# CPN_v1.net
KiCad netlist of a schematic drawn in EAGLE
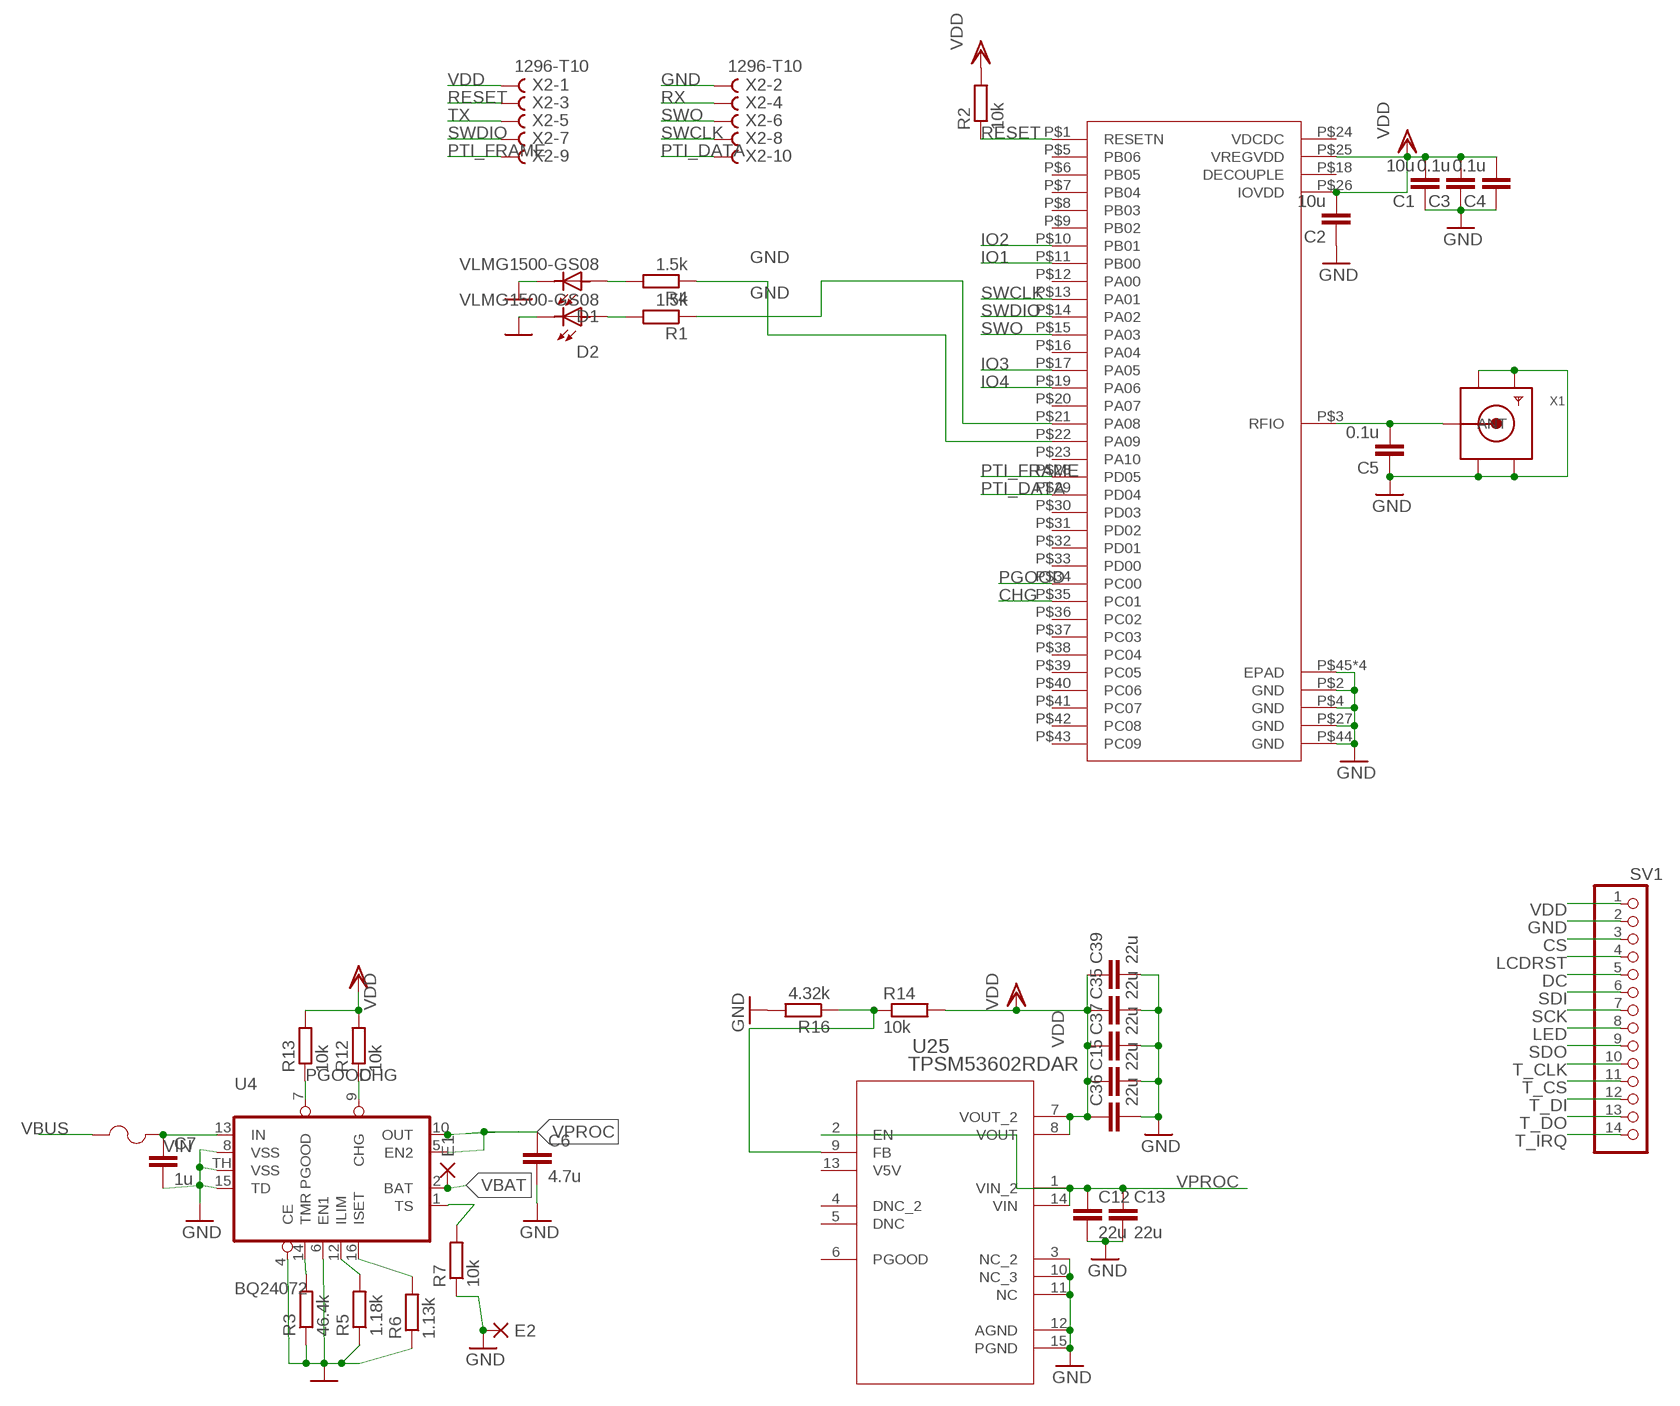
[diagram p0: schematic, sheet 1, part 1 of 2]
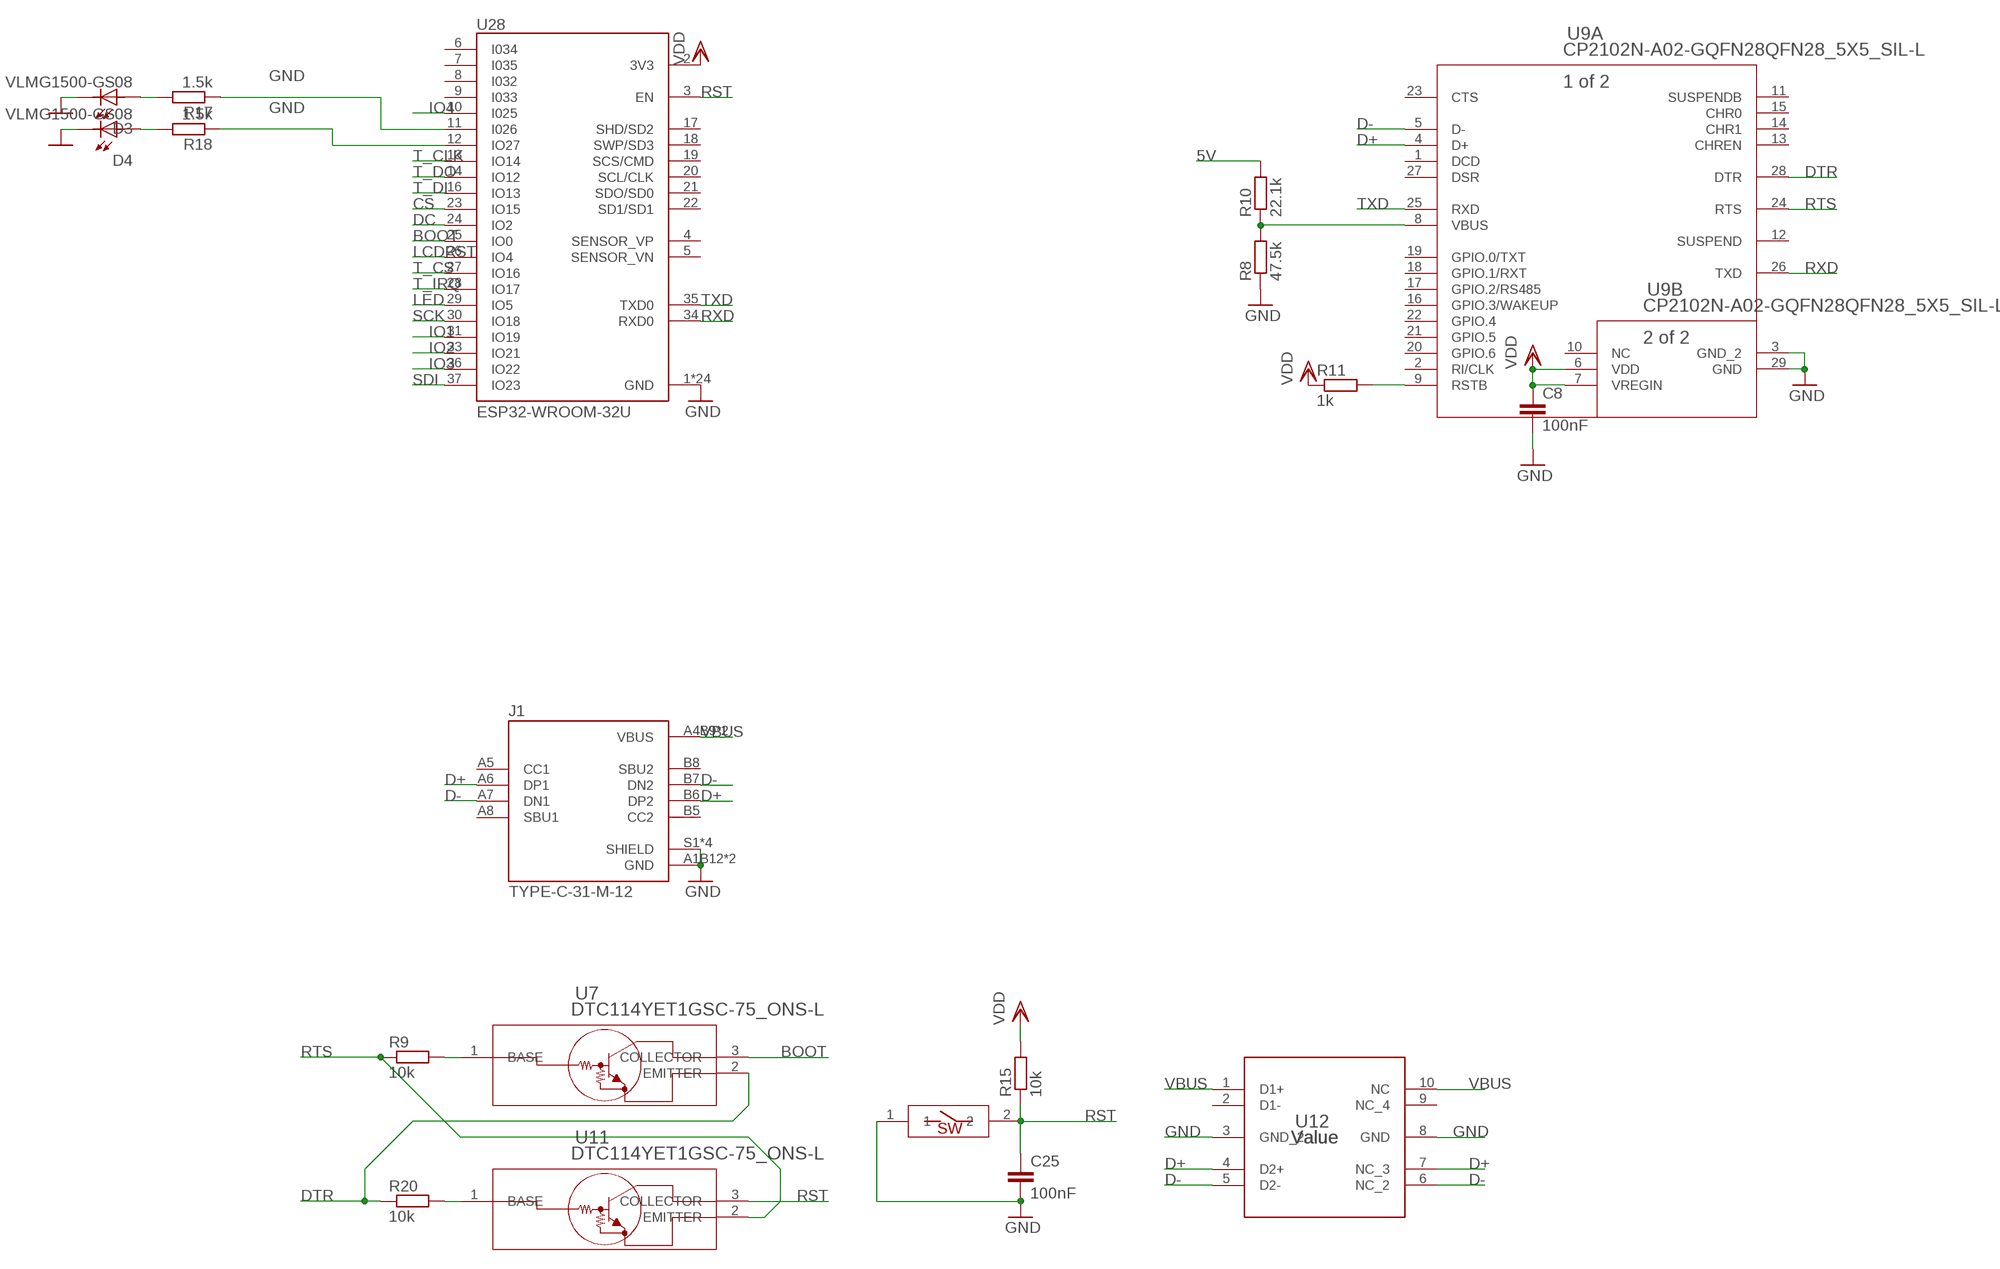
[diagram p1: schematic, sheet 1, part 2 of 2]

(export (version "E")
  (design (tool "Eeschema 10.0.6"))
  (components
    (comp (ref "C1")
      (value "10u")
      (footprint "eagle-import:C0603R")
      (libsource (lib "eagle-import") (part "CC0603R"))
    )
    (comp (ref "C2")
      (value "10u")
      (footprint "eagle-import:C0603R")
      (libsource (lib "eagle-import") (part "CC0603R"))
    )
    (comp (ref "C3")
      (value "0.1u")
      (footprint "eagle-import:C0402")
      (libsource (lib "eagle-import") (part "CC0402"))
    )
    (comp (ref "C4")
      (value "0.1u")
      (footprint "eagle-import:C0402")
      (libsource (lib "eagle-import") (part "CC0402"))
    )
    (comp (ref "C5")
      (value "0.1u")
      (footprint "eagle-import:C0402")
      (libsource (lib "eagle-import") (part "CC0402"))
    )
    (comp (ref "C6")
      (value "4.7u")
      (footprint "eagle-import:C0402")
      (libsource (lib "eagle-import") (part "CC0402"))
    )
    (comp (ref "C7")
      (value "1u")
      (footprint "eagle-import:C0402")
      (libsource (lib "eagle-import") (part "CC0402"))
    )
    (comp (ref "C8")
      (value "100nF")
      (footprint "eagle-import:C0402")
      (libsource (lib "eagle-import") (part "CC0402"))
    )
    (comp (ref "C12")
      (value "22u")
      (footprint "eagle-import:C0603R")
      (libsource (lib "eagle-import") (part "CC0603R"))
    )
    (comp (ref "C13")
      (value "22u")
      (footprint "eagle-import:C0603R")
      (libsource (lib "eagle-import") (part "CC0603R"))
    )
    (comp (ref "C15")
      (value "22u")
      (footprint "eagle-import:C0603R")
      (libsource (lib "eagle-import") (part "CC0603R"))
    )
    (comp (ref "C25")
      (value "100nF")
      (footprint "eagle-import:C0402")
      (libsource (lib "eagle-import") (part "CC0402"))
    )
    (comp (ref "C35")
      (value "22u")
      (footprint "eagle-import:C0603R")
      (libsource (lib "eagle-import") (part "CC0603R"))
    )
    (comp (ref "C36")
      (value "22u")
      (footprint "eagle-import:C0603R")
      (libsource (lib "eagle-import") (part "CC0603R"))
    )
    (comp (ref "C37")
      (value "22u")
      (footprint "eagle-import:C0603R")
      (libsource (lib "eagle-import") (part "CC0603R"))
    )
    (comp (ref "C39")
      (value "22u")
      (footprint "eagle-import:C0603R")
      (libsource (lib "eagle-import") (part "CC0603R"))
    )
    (comp (ref "D1")
      (value "VLMG1500-GS08")
      (footprint "eagle-import:LEDC1005X35N")
      (fields (field (name "MF") "Vishay"))
      (libsource (lib "eagle-import") (part "VLMG1500-GS08"))
    )
    (comp (ref "D2")
      (value "VLMG1500-GS08")
      (footprint "eagle-import:LEDC1005X35N")
      (fields (field (name "MF") "Vishay"))
      (libsource (lib "eagle-import") (part "VLMG1500-GS08"))
    )
    (comp (ref "D3")
      (value "VLMG1500-GS08")
      (footprint "eagle-import:LEDC1005X35N")
      (fields (field (name "MF") "Vishay"))
      (libsource (lib "eagle-import") (part "VLMG1500-GS08"))
    )
    (comp (ref "D4")
      (value "VLMG1500-GS08")
      (footprint "eagle-import:LEDC1005X35N")
      (fields (field (name "MF") "Vishay"))
      (libsource (lib "eagle-import") (part "VLMG1500-GS08"))
    )
    (comp (ref "E1")
      (value "DPADS_PAD-0400-S")
      (footprint "eagle-import:DPADS_0400-S")
      (libsource (lib "eagle-import") (part "DPADS_PAD-0400-S"))
    )
    (comp (ref "E2")
      (value "DPADS_PAD-0400-S")
      (footprint "eagle-import:DPADS_0400-S")
      (libsource (lib "eagle-import") (part "DPADS_PAD-0400-S"))
    )
    (comp (ref "F2")
      (value "1210L050YR1210LSERIES_LTF-L")
      (footprint "eagle-import:1210LSERIES_LTF-L")
      (fields (field (name "MANUFACTURER_PART_NUMBER") "1210L050YR"))
      (libsource (lib "eagle-import") (part "1210L050YR1210LSERIES_LTF-L"))
    )
    (comp (ref "J1")
      (value "TYPE-C-31-M-12")
      (footprint "eagle-import:HRO_TYPE-C-31-M-12")
      (fields (field (name "MF") "HRO Electronics Co., Ltd."))
      (libsource (lib "eagle-import") (part "TYPE-C-31-M-12"))
    )
    (comp (ref "R1")
      (value "1.5k")
      (footprint "eagle-import:R0402")
      (libsource (lib "eagle-import") (part "RR0402"))
    )
    (comp (ref "R2")
      (value "10k")
      (footprint "eagle-import:R0402")
      (libsource (lib "eagle-import") (part "RR0402"))
    )
    (comp (ref "R3")
      (value "46.4k")
      (footprint "eagle-import:R0402")
      (libsource (lib "eagle-import") (part "RR0402"))
    )
    (comp (ref "R4")
      (value "1.5k")
      (footprint "eagle-import:R0402")
      (libsource (lib "eagle-import") (part "RR0402"))
    )
    (comp (ref "R5")
      (value "1.18k")
      (footprint "eagle-import:R0402")
      (libsource (lib "eagle-import") (part "RR0402"))
    )
    (comp (ref "R6")
      (value "1.13k")
      (footprint "eagle-import:R0402")
      (libsource (lib "eagle-import") (part "RR0402"))
    )
    (comp (ref "R7")
      (value "10k")
      (footprint "eagle-import:R0402")
      (libsource (lib "eagle-import") (part "RR0402"))
    )
    (comp (ref "R8")
      (value "47.5k")
      (footprint "eagle-import:R0402")
      (libsource (lib "eagle-import") (part "RR0402"))
    )
    (comp (ref "R9")
      (value "10k")
      (footprint "eagle-import:R0402")
      (libsource (lib "eagle-import") (part "RR0402"))
    )
    (comp (ref "R10")
      (value "22.1k")
      (footprint "eagle-import:R0402")
      (libsource (lib "eagle-import") (part "RR0402"))
    )
    (comp (ref "R11")
      (value "1k")
      (footprint "eagle-import:R0402")
      (libsource (lib "eagle-import") (part "RR0402"))
    )
    (comp (ref "R12")
      (value "10k")
      (footprint "eagle-import:R0402")
      (libsource (lib "eagle-import") (part "RR0402"))
    )
    (comp (ref "R13")
      (value "10k")
      (footprint "eagle-import:R0402")
      (libsource (lib "eagle-import") (part "RR0402"))
    )
    (comp (ref "R14")
      (value "10k")
      (footprint "eagle-import:R0402")
      (libsource (lib "eagle-import") (part "RR0402"))
    )
    (comp (ref "R15")
      (value "10k")
      (footprint "eagle-import:R0402")
      (libsource (lib "eagle-import") (part "RR0402"))
    )
    (comp (ref "R16")
      (value "4.32k")
      (footprint "eagle-import:R0402")
      (libsource (lib "eagle-import") (part "RR0402"))
    )
    (comp (ref "R17")
      (value "1.5k")
      (footprint "eagle-import:R0402")
      (libsource (lib "eagle-import") (part "RR0402"))
    )
    (comp (ref "R18")
      (value "1.5k")
      (footprint "eagle-import:R0402")
      (libsource (lib "eagle-import") (part "RR0402"))
    )
    (comp (ref "R20")
      (value "10k")
      (footprint "eagle-import:R0402")
      (libsource (lib "eagle-import") (part "RR0402"))
    )
    (comp (ref "RESET")
      (value "SMDSWITCH")
      (footprint "eagle-import:RESC4217X170")
      (libsource (lib "eagle-import") (part "SMDSWITCH"))
    )
    (comp (ref "SV1")
      (value "PINHD-1X14")
      (footprint "eagle-import:1X14")
      (libsource (lib "eagle-import") (part "PINHD-1X14"))
    )
    (comp (ref "U$1")
      (value "ZGM230S")
      (footprint "eagle-import:ZGM230S")
      (libsource (lib "eagle-import") (part "ZGM230S"))
    )
    (comp (ref "U4")
      (value "BQ24072")
      (footprint "eagle-import:S-PVQFN-N16")
      (libsource (lib "eagle-import") (part "BQ24072"))
    )
    (comp (ref "U7")
      (value "DTC114YET1GSC-75_ONS-L")
      (footprint "eagle-import:SC-75_ONS-L")
      (fields
        (field (name "MANUFACTURER_PART_NUMBER") "DTC114YET1G")
        (field (name "COPYRIGHT") "Copyright (C) 2018 Accelerated Designs. All rights reserved")
      )
      (libsource (lib "eagle-import") (part "DTC114YET1GSC-75_ONS-L"))
    )
    (comp (ref "U9")
      (value "CP2102N-A02-GQFN28QFN28_5X5_SIL-L")
      (footprint "eagle-import:QFN28_5X5_SIL-L")
      (fields
        (field (name "MANUFACTURER_PART_NUMBER") "CP2102N-A02-GQFN28")
        (field (name "COPYRIGHT") "Copyright (C) 2018 Accelerated Designs. All rights reserved")
      )
      (libsource (lib "eagle-import") (part "CP2102N-A02-GQFN28QFN28_5X5_SIL-L"))
    )
    (comp (ref "U11")
      (value "DTC114YET1GSC-75_ONS-L")
      (footprint "eagle-import:SC-75_ONS-L")
      (fields
        (field (name "MANUFACTURER_PART_NUMBER") "DTC114YET1G")
        (field (name "COPYRIGHT") "Copyright (C) 2018 Accelerated Designs. All rights reserved")
      )
      (libsource (lib "eagle-import") (part "DTC114YET1GSC-75_ONS-L"))
    )
    (comp (ref "U12")
      (value "Value")
      (footprint "eagle-import:DQA0010A")
      (fields (field (name "MANUFACTURER") "Texas Instruments") (field (name "PARTNUMBER") "ESD204DQAR"))
      (libsource (lib "eagle-import") (part "ESD204DQAR"))
    )
    (comp (ref "U25")
      (value "TPSM53602RDAR")
      (footprint "eagle-import:B3QFN15_RDA_TEX")
      (fields (field (name "COPYRIGHT") "Copyright (C) 2018 Accelerated Designs. All rights reserved"))
      (libsource (lib "eagle-import") (part "TPSM53602RDAR"))
    )
    (comp (ref "U28")
      (value "ESP32-WROOM-32U")
      (footprint "eagle-import:XCVR_ESP32-WROOM-32U")
      (fields (field (name "MF") "Espressif Systems"))
      (libsource (lib "eagle-import") (part "ESP32-WROOM-32U"))
    )
    (comp (ref "X1")
      (value "SMACONNECTOR")
      (footprint "eagle-import:SMA90_DIP")
      (libsource (lib "eagle-import") (part "SMACONNECTOR"))
    )
    (comp (ref "X2")
      (value "1296-T10")
      (footprint "eagle-import:1296-10")
      (libsource (lib "eagle-import") (part "1296-T10"))
    )
  )
  (nets
    (net (code "1") (name "/5V") (class "Default")
      (node (ref "R10") (pin "2") (pinfunction "2_2") (pintype "passive"))
    )
    (net (code "2") (name "/BOOT") (class "Default")
      (node (ref "U28") (pin "25") (pinfunction "IO0_25") (pintype "bidirectional"))
      (node (ref "U7") (pin "3") (pinfunction "COLLECTOR_3") (pintype "output"))
    )
    (net (code "3") (name "/CHG") (class "Default")
      (node (ref "R12") (pin "1") (pinfunction "1_1") (pintype "passive"))
      (node (ref "U$1") (pin "P$35") (pinfunction "PC01_P$35") (pintype "bidirectional"))
      (node (ref "U4") (pin "9") (pinfunction "CHG_9") (pintype "bidirectional"))
    )
    (net (code "4") (name "/CS") (class "Default")
      (node (ref "SV1") (pin "3") (pinfunction "3_3") (pintype "passive"))
      (node (ref "U28") (pin "23") (pinfunction "IO15_23") (pintype "bidirectional"))
    )
    (net (code "5") (name "/D+") (class "Default")
      (node (ref "J1") (pin "A6") (pinfunction "DP1_A6") (pintype "bidirectional"))
      (node (ref "J1") (pin "B6") (pinfunction "DP2_B6") (pintype "bidirectional"))
      (node (ref "U12") (pin "4") (pinfunction "D2+_4") (pintype "bidirectional"))
      (node (ref "U12") (pin "7") (pinfunction "NC_3_7") (pintype "passive"))
      (node (ref "U9") (pin "4") (pinfunction "D+_4") (pintype "input"))
    )
    (net (code "6") (name "/D-") (class "Default")
      (node (ref "J1") (pin "A7") (pinfunction "DN1_A7") (pintype "bidirectional"))
      (node (ref "J1") (pin "B7") (pinfunction "DN2_B7") (pintype "bidirectional"))
      (node (ref "U12") (pin "5") (pinfunction "D2-_5") (pintype "bidirectional"))
      (node (ref "U12") (pin "6") (pinfunction "NC_2_6") (pintype "passive"))
      (node (ref "U9") (pin "5") (pinfunction "D-_5") (pintype "input"))
    )
    (net (code "7") (name "/DC") (class "Default")
      (node (ref "SV1") (pin "5") (pinfunction "5_5") (pintype "passive"))
      (node (ref "U28") (pin "24") (pinfunction "IO2_24") (pintype "bidirectional"))
    )
    (net (code "8") (name "/DTR") (class "Default")
      (node (ref "R20") (pin "1") (pinfunction "1_1") (pintype "passive"))
      (node (ref "U7") (pin "2") (pinfunction "EMITTER_2") (pintype "passive"))
      (node (ref "U9") (pin "28") (pinfunction "DTR_28") (pintype "output"))
    )
    (net (code "9") (name "/IO1") (class "Default")
      (node (ref "U$1") (pin "P$11") (pinfunction "PB00_P$11") (pintype "bidirectional"))
      (node (ref "U28") (pin "31") (pinfunction "IO19_31") (pintype "bidirectional"))
    )
    (net (code "10") (name "/IO2") (class "Default")
      (node (ref "U$1") (pin "P$10") (pinfunction "PB01_P$10") (pintype "bidirectional"))
      (node (ref "U28") (pin "33") (pinfunction "IO21_33") (pintype "bidirectional"))
    )
    (net (code "11") (name "/IO3") (class "Default")
      (node (ref "U$1") (pin "P$17") (pinfunction "PA05_P$17") (pintype "bidirectional"))
      (node (ref "U28") (pin "36") (pinfunction "IO22_36") (pintype "bidirectional"))
    )
    (net (code "12") (name "/IO4") (class "Default")
      (node (ref "U$1") (pin "P$19") (pinfunction "PA06_P$19") (pintype "bidirectional"))
      (node (ref "U28") (pin "10") (pinfunction "I025_10") (pintype "bidirectional"))
    )
    (net (code "13") (name "/LCDRST") (class "Default")
      (node (ref "SV1") (pin "4") (pinfunction "4_4") (pintype "passive"))
      (node (ref "U28") (pin "26") (pinfunction "IO4_26") (pintype "bidirectional"))
    )
    (net (code "14") (name "/LED") (class "Default")
      (node (ref "SV1") (pin "8") (pinfunction "8_8") (pintype "passive"))
      (node (ref "U28") (pin "29") (pinfunction "IO5_29") (pintype "bidirectional"))
    )
    (net (code "15") (name "/PGOOD") (class "Default")
      (node (ref "R13") (pin "1") (pinfunction "1_1") (pintype "passive"))
      (node (ref "U$1") (pin "P$34") (pinfunction "PC00_P$34") (pintype "bidirectional"))
      (node (ref "U4") (pin "7") (pinfunction "PGOOD_7") (pintype "bidirectional"))
    )
    (net (code "16") (name "/PTI_DATA") (class "Default")
      (node (ref "U$1") (pin "P$29") (pinfunction "PD04_P$29") (pintype "bidirectional"))
      (node (ref "X2") (pin "10") (pinfunction "B_10") (pintype "passive"))
    )
    (net (code "17") (name "/PTI_FRAME") (class "Default")
      (node (ref "U$1") (pin "P$28") (pinfunction "PD05_P$28") (pintype "bidirectional"))
      (node (ref "X2") (pin "9") (pinfunction "B_9") (pintype "passive"))
    )
    (net (code "18") (name "/RESET") (class "Default")
      (node (ref "R2") (pin "1") (pinfunction "1_1") (pintype "passive"))
      (node (ref "U$1") (pin "P$1") (pinfunction "RESETN_P$1") (pintype "bidirectional"))
      (node (ref "X2") (pin "3") (pinfunction "B_3") (pintype "passive"))
    )
    (net (code "19") (name "/RST") (class "Default")
      (node (ref "C25") (pin "1") (pinfunction "1_1") (pintype "passive"))
      (node (ref "R15") (pin "1") (pinfunction "1_1") (pintype "passive"))
      (node (ref "RESET") (pin "2") (pinfunction "2_2") (pintype "bidirectional"))
      (node (ref "U11") (pin "3") (pinfunction "COLLECTOR_3") (pintype "output"))
      (node (ref "U28") (pin "3") (pinfunction "EN_3") (pintype "input"))
    )
    (net (code "20") (name "/RTS") (class "Default")
      (node (ref "R9") (pin "1") (pinfunction "1_1") (pintype "passive"))
      (node (ref "U11") (pin "2") (pinfunction "EMITTER_2") (pintype "passive"))
      (node (ref "U9") (pin "24") (pinfunction "RTS_24") (pintype "output"))
    )
    (net (code "21") (name "/RX") (class "Default")
      (node (ref "X2") (pin "4") (pinfunction "B_4") (pintype "passive"))
    )
    (net (code "22") (name "/RXD") (class "Default")
      (node (ref "U28") (pin "34") (pinfunction "RXD0_34") (pintype "bidirectional"))
      (node (ref "U9") (pin "26") (pinfunction "TXD_26") (pintype "output"))
    )
    (net (code "23") (name "/SCK") (class "Default")
      (node (ref "SV1") (pin "7") (pinfunction "7_7") (pintype "passive"))
      (node (ref "U28") (pin "30") (pinfunction "IO18_30") (pintype "bidirectional"))
    )
    (net (code "24") (name "/SDI") (class "Default")
      (node (ref "SV1") (pin "6") (pinfunction "6_6") (pintype "passive"))
      (node (ref "U28") (pin "37") (pinfunction "IO23_37") (pintype "bidirectional"))
    )
    (net (code "25") (name "/SDO") (class "Default")
      (node (ref "SV1") (pin "9") (pinfunction "9_9") (pintype "passive"))
    )
    (net (code "26") (name "/SWCLK") (class "Default")
      (node (ref "U$1") (pin "P$13") (pinfunction "PA01_P$13") (pintype "bidirectional"))
      (node (ref "X2") (pin "8") (pinfunction "B_8") (pintype "passive"))
    )
    (net (code "27") (name "/SWDIO") (class "Default")
      (node (ref "U$1") (pin "P$14") (pinfunction "PA02_P$14") (pintype "bidirectional"))
      (node (ref "X2") (pin "7") (pinfunction "B_7") (pintype "passive"))
    )
    (net (code "28") (name "/SWO") (class "Default")
      (node (ref "U$1") (pin "P$15") (pinfunction "PA03_P$15") (pintype "bidirectional"))
      (node (ref "X2") (pin "6") (pinfunction "B_6") (pintype "passive"))
    )
    (net (code "29") (name "/TX") (class "Default")
      (node (ref "X2") (pin "5") (pinfunction "B_5") (pintype "passive"))
    )
    (net (code "30") (name "/TXD") (class "Default")
      (node (ref "U28") (pin "35") (pinfunction "TXD0_35") (pintype "bidirectional"))
      (node (ref "U9") (pin "25") (pinfunction "RXD_25") (pintype "input"))
    )
    (net (code "31") (name "/T_CLK") (class "Default")
      (node (ref "SV1") (pin "10") (pinfunction "10_10") (pintype "passive"))
      (node (ref "U28") (pin "13") (pinfunction "IO14_13") (pintype "bidirectional"))
    )
    (net (code "32") (name "/T_CS") (class "Default")
      (node (ref "SV1") (pin "11") (pinfunction "11_11") (pintype "passive"))
      (node (ref "U28") (pin "27") (pinfunction "IO16_27") (pintype "bidirectional"))
    )
    (net (code "33") (name "/T_DI") (class "Default")
      (node (ref "SV1") (pin "12") (pinfunction "12_12") (pintype "passive"))
      (node (ref "U28") (pin "16") (pinfunction "IO13_16") (pintype "bidirectional"))
    )
    (net (code "34") (name "/T_DO") (class "Default")
      (node (ref "SV1") (pin "13") (pinfunction "13_13") (pintype "passive"))
      (node (ref "U28") (pin "14") (pinfunction "IO12_14") (pintype "bidirectional"))
    )
    (net (code "35") (name "/T_IRQ") (class "Default")
      (node (ref "SV1") (pin "14") (pinfunction "14_14") (pintype "passive"))
      (node (ref "U28") (pin "28") (pinfunction "IO17_28") (pintype "bidirectional"))
    )
    (net (code "36") (name "/VBUS") (class "Default")
      (node (ref "F2") (pin "1") (pinfunction "1_1") (pintype "passive"))
      (node (ref "J1") (pin "A4B9") (pinfunction "VBUS_A4B9") (pintype "power_in"))
      (node (ref "J1") (pin "B4A9") (pinfunction "VBUS_B4A9") (pintype "power_in"))
      (node (ref "U12") (pin "1") (pinfunction "D1+_1") (pintype "bidirectional"))
      (node (ref "U12") (pin "10") (pinfunction "NC_10") (pintype "passive"))
    )
    (net (code "37") (name "/VIN") (class "Default")
      (node (ref "C7") (pin "1") (pinfunction "1_1") (pintype "passive"))
      (node (ref "F2") (pin "2") (pinfunction "2_2") (pintype "passive"))
      (node (ref "U4") (pin "13") (pinfunction "IN_13") (pintype "input"))
    )
    (net (code "38") (name "GND") (class "Default")
      (node (ref "C1") (pin "1") (pinfunction "1_1") (pintype "passive"))
      (node (ref "C12") (pin "2") (pinfunction "2_2") (pintype "passive"))
      (node (ref "C13") (pin "2") (pinfunction "2_2") (pintype "passive"))
      (node (ref "C15") (pin "2") (pinfunction "2_2") (pintype "passive"))
      (node (ref "C2") (pin "1") (pinfunction "1_1") (pintype "passive"))
      (node (ref "C25") (pin "2") (pinfunction "2_2") (pintype "passive"))
      (node (ref "C3") (pin "1") (pinfunction "1_1") (pintype "passive"))
      (node (ref "C35") (pin "2") (pinfunction "2_2") (pintype "passive"))
      (node (ref "C36") (pin "2") (pinfunction "2_2") (pintype "passive"))
      (node (ref "C37") (pin "2") (pinfunction "2_2") (pintype "passive"))
      (node (ref "C39") (pin "2") (pinfunction "2_2") (pintype "passive"))
      (node (ref "C4") (pin "1") (pinfunction "1_1") (pintype "passive"))
      (node (ref "C5") (pin "1") (pinfunction "1_1") (pintype "passive"))
      (node (ref "C6") (pin "2") (pinfunction "2_2") (pintype "passive"))
      (node (ref "C7") (pin "2") (pinfunction "2_2") (pintype "passive"))
      (node (ref "C8") (pin "2") (pinfunction "2_2") (pintype "passive"))
      (node (ref "D1") (pin "2") (pinfunction "2_2") (pintype "passive"))
      (node (ref "D2") (pin "2") (pinfunction "2_2") (pintype "passive"))
      (node (ref "D3") (pin "2") (pinfunction "2_2") (pintype "passive"))
      (node (ref "D4") (pin "2") (pinfunction "2_2") (pintype "passive"))
      (node (ref "E2") (pin "PAD") (pinfunction "P_PAD") (pintype "passive"))
      (node (ref "J1") (pin "A1B12") (pinfunction "GND_A1B12") (pintype "power_in"))
      (node (ref "J1") (pin "B1A12") (pinfunction "GND_B1A12") (pintype "power_in"))
      (node (ref "J1") (pin "S1") (pinfunction "SHIELD_S1") (pintype "passive"))
      (node (ref "J1") (pin "S2") (pinfunction "SHIELD_S2") (pintype "passive"))
      (node (ref "J1") (pin "S3") (pinfunction "SHIELD_S3") (pintype "passive"))
      (node (ref "J1") (pin "S4") (pinfunction "SHIELD_S4") (pintype "passive"))
      (node (ref "R16") (pin "2") (pinfunction "2_2") (pintype "passive"))
      (node (ref "R3") (pin "1") (pinfunction "1_1") (pintype "passive"))
      (node (ref "R5") (pin "1") (pinfunction "1_1") (pintype "passive"))
      (node (ref "R6") (pin "1") (pinfunction "1_1") (pintype "passive"))
      (node (ref "R7") (pin "1") (pinfunction "1_1") (pintype "passive"))
      (node (ref "R8") (pin "1") (pinfunction "1_1") (pintype "passive"))
      (node (ref "RESET") (pin "1") (pinfunction "1_1") (pintype "bidirectional"))
      (node (ref "SV1") (pin "2") (pinfunction "2_2") (pintype "passive"))
      (node (ref "U$1") (pin "P$2") (pinfunction "GND_P$2") (pintype "bidirectional"))
      (node (ref "U$1") (pin "P$27") (pinfunction "GND_P$27") (pintype "bidirectional"))
      (node (ref "U$1") (pin "P$4") (pinfunction "GND_P$4") (pintype "bidirectional"))
      (node (ref "U$1") (pin "P$44") (pinfunction "GND_P$44") (pintype "bidirectional"))
      (node (ref "U$1") (pin "P$45") (pinfunction "EPAD_P$45") (pintype "bidirectional"))
      (node (ref "U$1") (pin "P$46") (pinfunction "EPAD_P$46") (pintype "bidirectional"))
      (node (ref "U$1") (pin "P$47") (pinfunction "EPAD_P$47") (pintype "bidirectional"))
      (node (ref "U$1") (pin "P$48") (pinfunction "EPAD_P$48") (pintype "bidirectional"))
      (node (ref "U12") (pin "3") (pinfunction "GND_2_3") (pintype "power_in"))
      (node (ref "U12") (pin "8") (pinfunction "GND_8") (pintype "power_in"))
      (node (ref "U25") (pin "10") (pinfunction "NC_3_10") (pintype "passive"))
      (node (ref "U25") (pin "11") (pinfunction "NC_11") (pintype "passive"))
      (node (ref "U25") (pin "12") (pinfunction "AGND_12") (pintype "passive"))
      (node (ref "U25") (pin "15") (pinfunction "PGND_15") (pintype "passive"))
      (node (ref "U25") (pin "3") (pinfunction "NC_2_3") (pintype "passive"))
      (node (ref "U28") (pin "1") (pinfunction "GND_1") (pintype "power_in"))
      (node (ref "U28") (pin "15") (pinfunction "GND_15") (pintype "power_in"))
      (node (ref "U28") (pin "38") (pinfunction "GND_38") (pintype "power_in"))
      (node (ref "U28") (pin "G.1") (pinfunction "GND_G.1") (pintype "power_in"))
      (node (ref "U28") (pin "G.10") (pinfunction "GND_G.10") (pintype "power_in"))
      (node (ref "U28") (pin "G.11") (pinfunction "GND_G.11") (pintype "power_in"))
      (node (ref "U28") (pin "G.12") (pinfunction "GND_G.12") (pintype "power_in"))
      (node (ref "U28") (pin "G.13") (pinfunction "GND_G.13") (pintype "power_in"))
      (node (ref "U28") (pin "G.14") (pinfunction "GND_G.14") (pintype "power_in"))
      (node (ref "U28") (pin "G.15") (pinfunction "GND_G.15") (pintype "power_in"))
      (node (ref "U28") (pin "G.16") (pinfunction "GND_G.16") (pintype "power_in"))
      (node (ref "U28") (pin "G.17") (pinfunction "GND_G.17") (pintype "power_in"))
      (node (ref "U28") (pin "G.18") (pinfunction "GND_G.18") (pintype "power_in"))
      (node (ref "U28") (pin "G.19") (pinfunction "GND_G.19") (pintype "power_in"))
      (node (ref "U28") (pin "G.2") (pinfunction "GND_G.2") (pintype "power_in"))
      (node (ref "U28") (pin "G.20") (pinfunction "GND_G.20") (pintype "power_in"))
      (node (ref "U28") (pin "G.21") (pinfunction "GND_G.21") (pintype "power_in"))
      (node (ref "U28") (pin "G.22") (pinfunction "GND_G.22") (pintype "power_in"))
      (node (ref "U28") (pin "G.4") (pinfunction "GND_G.4") (pintype "power_in"))
      (node (ref "U28") (pin "G.5") (pinfunction "GND_G.5") (pintype "power_in"))
      (node (ref "U28") (pin "G.6") (pinfunction "GND_G.6") (pintype "power_in"))
      (node (ref "U28") (pin "G.7") (pinfunction "GND_G.7") (pintype "power_in"))
      (node (ref "U28") (pin "G.8") (pinfunction "GND_G.8") (pintype "power_in"))
      (node (ref "U28") (pin "G.9") (pinfunction "GND_G.9") (pintype "power_in"))
      (node (ref "U4") (pin "15") (pinfunction "TD_15") (pintype "bidirectional"))
      (node (ref "U4") (pin "4") (pinfunction "CE_4") (pintype "bidirectional"))
      (node (ref "U4") (pin "6") (pinfunction "EN1_6") (pintype "bidirectional"))
      (node (ref "U4") (pin "8") (pinfunction "VSS_8") (pintype "power_in"))
      (node (ref "U4") (pin "TH") (pinfunction "VSS_TH") (pintype "power_in"))
      (node (ref "U9") (pin "29") (pinfunction "GND_29") (pintype "passive"))
      (node (ref "U9") (pin "3") (pinfunction "GND_2_3") (pintype "passive"))
      (node (ref "X1") (pin "GND1") (pinfunction "GND1_GND1") (pintype "power_in"))
      (node (ref "X1") (pin "GND2") (pinfunction "GND2_GND2") (pintype "power_in"))
      (node (ref "X1") (pin "GND3") (pinfunction "GND3_GND3") (pintype "power_in"))
      (node (ref "X1") (pin "GND4") (pinfunction "GND4_GND4") (pintype "power_in"))
      (node (ref "X2") (pin "2") (pinfunction "B_2") (pintype "passive"))
    )
    (net (code "39") (name "Net-(D1-Pad1)") (class "Default")
      (node (ref "D1") (pin "1") (pinfunction "1_1") (pintype "passive"))
      (node (ref "R4") (pin "2") (pinfunction "2_2") (pintype "passive"))
    )
    (net (code "40") (name "Net-(D2-Pad1)") (class "Default")
      (node (ref "D2") (pin "1") (pinfunction "1_1") (pintype "passive"))
      (node (ref "R1") (pin "2") (pinfunction "2_2") (pintype "passive"))
    )
    (net (code "41") (name "Net-(D3-Pad1)") (class "Default")
      (node (ref "D3") (pin "1") (pinfunction "1_1") (pintype "passive"))
      (node (ref "R17") (pin "2") (pinfunction "2_2") (pintype "passive"))
    )
    (net (code "42") (name "Net-(D4-Pad1)") (class "Default")
      (node (ref "D4") (pin "1") (pinfunction "1_1") (pintype "passive"))
      (node (ref "R18") (pin "2") (pinfunction "2_2") (pintype "passive"))
    )
    (net (code "43") (name "Net-(U$1-PA08)") (class "Default")
      (node (ref "R1") (pin "1") (pinfunction "1_1") (pintype "passive"))
      (node (ref "U$1") (pin "P$21") (pinfunction "PA08_P$21") (pintype "bidirectional"))
    )
    (net (code "44") (name "Net-(U$1-PA09)") (class "Default")
      (node (ref "R4") (pin "1") (pinfunction "1_1") (pintype "passive"))
      (node (ref "U$1") (pin "P$22") (pinfunction "PA09_P$22") (pintype "bidirectional"))
    )
    (net (code "45") (name "Net-(U$1-RFIO)") (class "Default")
      (node (ref "C5") (pin "2") (pinfunction "2_2") (pintype "passive"))
      (node (ref "U$1") (pin "P$3") (pinfunction "RFIO_P$3") (pintype "bidirectional"))
      (node (ref "X1") (pin "ANTENNA") (pinfunction "ANT_ANTENNA") (pintype "bidirectional"))
    )
    (net (code "46") (name "Net-(U4-ILIM)") (class "Default")
      (node (ref "R5") (pin "2") (pinfunction "2_2") (pintype "passive"))
      (node (ref "U4") (pin "12") (pinfunction "ILIM_12") (pintype "bidirectional"))
    )
    (net (code "47") (name "Net-(U4-ISET)") (class "Default")
      (node (ref "R6") (pin "2") (pinfunction "2_2") (pintype "passive"))
      (node (ref "U4") (pin "16") (pinfunction "ISET_16") (pintype "input"))
    )
    (net (code "48") (name "Net-(U4-TMR)") (class "Default")
      (node (ref "R3") (pin "2") (pinfunction "2_2") (pintype "passive"))
      (node (ref "U4") (pin "14") (pinfunction "TMR_14") (pintype "bidirectional"))
    )
    (net (code "49") (name "Net-(U4-TS)") (class "Default")
      (node (ref "R7") (pin "2") (pinfunction "2_2") (pintype "passive"))
      (node (ref "U4") (pin "1") (pinfunction "TS_1") (pintype "input"))
    )
    (net (code "50") (name "Net-(U7-BASE)") (class "Default")
      (node (ref "R9") (pin "2") (pinfunction "2_2") (pintype "passive"))
      (node (ref "U7") (pin "1") (pinfunction "BASE_1") (pintype "input"))
    )
    (net (code "51") (name "Net-(U9A-RSTB)") (class "Default")
      (node (ref "R11") (pin "2") (pinfunction "2_2") (pintype "passive"))
      (node (ref "U9") (pin "9") (pinfunction "RSTB_9") (pintype "passive"))
    )
    (net (code "52") (name "Net-(U9A-VBUS)") (class "Default")
      (node (ref "R10") (pin "1") (pinfunction "1_1") (pintype "passive"))
      (node (ref "R8") (pin "2") (pinfunction "2_2") (pintype "passive"))
      (node (ref "U9") (pin "8") (pinfunction "VBUS_8") (pintype "input"))
    )
    (net (code "53") (name "Net-(U11-BASE)") (class "Default")
      (node (ref "R20") (pin "2") (pinfunction "2_2") (pintype "passive"))
      (node (ref "U11") (pin "1") (pinfunction "BASE_1") (pintype "input"))
    )
    (net (code "54") (name "Net-(U25-FB)") (class "Default")
      (node (ref "R14") (pin "1") (pinfunction "1_1") (pintype "passive"))
      (node (ref "R16") (pin "1") (pinfunction "1_1") (pintype "passive"))
      (node (ref "U25") (pin "9") (pinfunction "FB_9") (pintype "passive"))
    )
    (net (code "55") (name "Net-(U28-I026)") (class "Default")
      (node (ref "R17") (pin "1") (pinfunction "1_1") (pintype "passive"))
      (node (ref "U28") (pin "11") (pinfunction "I026_11") (pintype "bidirectional"))
    )
    (net (code "56") (name "Net-(U28-IO27)") (class "Default")
      (node (ref "R18") (pin "1") (pinfunction "1_1") (pintype "passive"))
      (node (ref "U28") (pin "12") (pinfunction "IO27_12") (pintype "bidirectional"))
    )
    (net (code "57") (name "VBAT") (class "Default")
      (node (ref "E1") (pin "PAD") (pinfunction "P_PAD") (pintype "passive"))
      (node (ref "U4") (pin "2") (pinfunction "BAT_2") (pintype "input"))
    )
    (net (code "58") (name "VDD") (class "Default")
      (node (ref "C1") (pin "2") (pinfunction "2_2") (pintype "passive"))
      (node (ref "C15") (pin "1") (pinfunction "1_1") (pintype "passive"))
      (node (ref "C2") (pin "2") (pinfunction "2_2") (pintype "passive"))
      (node (ref "C3") (pin "2") (pinfunction "2_2") (pintype "passive"))
      (node (ref "C35") (pin "1") (pinfunction "1_1") (pintype "passive"))
      (node (ref "C36") (pin "1") (pinfunction "1_1") (pintype "passive"))
      (node (ref "C37") (pin "1") (pinfunction "1_1") (pintype "passive"))
      (node (ref "C39") (pin "1") (pinfunction "1_1") (pintype "passive"))
      (node (ref "C4") (pin "2") (pinfunction "2_2") (pintype "passive"))
      (node (ref "C8") (pin "1") (pinfunction "1_1") (pintype "passive"))
      (node (ref "R11") (pin "1") (pinfunction "1_1") (pintype "passive"))
      (node (ref "R12") (pin "2") (pinfunction "2_2") (pintype "passive"))
      (node (ref "R13") (pin "2") (pinfunction "2_2") (pintype "passive"))
      (node (ref "R14") (pin "2") (pinfunction "2_2") (pintype "passive"))
      (node (ref "R15") (pin "2") (pinfunction "2_2") (pintype "passive"))
      (node (ref "R2") (pin "2") (pinfunction "2_2") (pintype "passive"))
      (node (ref "SV1") (pin "1") (pinfunction "1_1") (pintype "passive"))
      (node (ref "U$1") (pin "P$25") (pinfunction "VREGVDD_P$25") (pintype "bidirectional"))
      (node (ref "U$1") (pin "P$26") (pinfunction "IOVDD_P$26") (pintype "bidirectional"))
      (node (ref "U25") (pin "7") (pinfunction "VOUT_2_7") (pintype "passive"))
      (node (ref "U25") (pin "8") (pinfunction "VOUT_8") (pintype "passive"))
      (node (ref "U28") (pin "2") (pinfunction "3V3_2") (pintype "power_in"))
      (node (ref "U9") (pin "6") (pinfunction "VDD_6") (pintype "power_in"))
      (node (ref "U9") (pin "7") (pinfunction "VREGIN_7") (pintype "power_in"))
      (node (ref "X2") (pin "1") (pinfunction "B_1") (pintype "passive"))
    )
    (net (code "59") (name "VPROC") (class "Default")
      (node (ref "C12") (pin "1") (pinfunction "1_1") (pintype "passive"))
      (node (ref "C13") (pin "1") (pinfunction "1_1") (pintype "passive"))
      (node (ref "C6") (pin "1") (pinfunction "1_1") (pintype "passive"))
      (node (ref "U25") (pin "1") (pinfunction "VIN_2_1") (pintype "passive"))
      (node (ref "U25") (pin "14") (pinfunction "VIN_14") (pintype "passive"))
      (node (ref "U25") (pin "2") (pinfunction "EN_2") (pintype "passive"))
      (node (ref "U4") (pin "10") (pinfunction "OUT_10") (pintype "output"))
      (node (ref "U4") (pin "5") (pinfunction "EN2_5") (pintype "input"))
    )
    (net (code "60") (name "unconnected-(J1-CC1-PadA5)") (class "Default")
      (node (ref "J1") (pin "A5") (pinfunction "CC1_A5") (pintype "bidirectional"))
    )
    (net (code "61") (name "unconnected-(J1-CC2-PadB5)") (class "Default")
      (node (ref "J1") (pin "B5") (pinfunction "CC2_B5") (pintype "bidirectional"))
    )
    (net (code "62") (name "unconnected-(J1-SBU1-PadA8)") (class "Default")
      (node (ref "J1") (pin "A8") (pinfunction "SBU1_A8") (pintype "bidirectional"))
    )
    (net (code "63") (name "unconnected-(J1-SBU2-PadB8)") (class "Default")
      (node (ref "J1") (pin "B8") (pinfunction "SBU2_B8") (pintype "bidirectional"))
    )
    (net (code "64") (name "unconnected-(U$1-DECOUPLE-PadP$18)") (class "Default")
      (node (ref "U$1") (pin "P$18") (pinfunction "DECOUPLE_P$18") (pintype "bidirectional"))
    )
    (net (code "65") (name "unconnected-(U$1-PA00-PadP$12)") (class "Default")
      (node (ref "U$1") (pin "P$12") (pinfunction "PA00_P$12") (pintype "bidirectional"))
    )
    (net (code "66") (name "unconnected-(U$1-PA04-PadP$16)") (class "Default")
      (node (ref "U$1") (pin "P$16") (pinfunction "PA04_P$16") (pintype "bidirectional"))
    )
    (net (code "67") (name "unconnected-(U$1-PA07-PadP$20)") (class "Default")
      (node (ref "U$1") (pin "P$20") (pinfunction "PA07_P$20") (pintype "bidirectional"))
    )
    (net (code "68") (name "unconnected-(U$1-PA10-PadP$23)") (class "Default")
      (node (ref "U$1") (pin "P$23") (pinfunction "PA10_P$23") (pintype "bidirectional"))
    )
    (net (code "69") (name "unconnected-(U$1-PB02-PadP$9)") (class "Default")
      (node (ref "U$1") (pin "P$9") (pinfunction "PB02_P$9") (pintype "bidirectional"))
    )
    (net (code "70") (name "unconnected-(U$1-PB03-PadP$8)") (class "Default")
      (node (ref "U$1") (pin "P$8") (pinfunction "PB03_P$8") (pintype "bidirectional"))
    )
    (net (code "71") (name "unconnected-(U$1-PB04-PadP$7)") (class "Default")
      (node (ref "U$1") (pin "P$7") (pinfunction "PB04_P$7") (pintype "bidirectional"))
    )
    (net (code "72") (name "unconnected-(U$1-PB05-PadP$6)") (class "Default")
      (node (ref "U$1") (pin "P$6") (pinfunction "PB05_P$6") (pintype "bidirectional"))
    )
    (net (code "73") (name "unconnected-(U$1-PB06-PadP$5)") (class "Default")
      (node (ref "U$1") (pin "P$5") (pinfunction "PB06_P$5") (pintype "bidirectional"))
    )
    (net (code "74") (name "unconnected-(U$1-PC02-PadP$36)") (class "Default")
      (node (ref "U$1") (pin "P$36") (pinfunction "PC02_P$36") (pintype "bidirectional"))
    )
    (net (code "75") (name "unconnected-(U$1-PC03-PadP$37)") (class "Default")
      (node (ref "U$1") (pin "P$37") (pinfunction "PC03_P$37") (pintype "bidirectional"))
    )
    (net (code "76") (name "unconnected-(U$1-PC04-PadP$38)") (class "Default")
      (node (ref "U$1") (pin "P$38") (pinfunction "PC04_P$38") (pintype "bidirectional"))
    )
    (net (code "77") (name "unconnected-(U$1-PC05-PadP$39)") (class "Default")
      (node (ref "U$1") (pin "P$39") (pinfunction "PC05_P$39") (pintype "bidirectional"))
    )
    (net (code "78") (name "unconnected-(U$1-PC06-PadP$40)") (class "Default")
      (node (ref "U$1") (pin "P$40") (pinfunction "PC06_P$40") (pintype "bidirectional"))
    )
    (net (code "79") (name "unconnected-(U$1-PC07-PadP$41)") (class "Default")
      (node (ref "U$1") (pin "P$41") (pinfunction "PC07_P$41") (pintype "bidirectional"))
    )
    (net (code "80") (name "unconnected-(U$1-PC08-PadP$42)") (class "Default")
      (node (ref "U$1") (pin "P$42") (pinfunction "PC08_P$42") (pintype "bidirectional"))
    )
    (net (code "81") (name "unconnected-(U$1-PC09-PadP$43)") (class "Default")
      (node (ref "U$1") (pin "P$43") (pinfunction "PC09_P$43") (pintype "bidirectional"))
    )
    (net (code "82") (name "unconnected-(U$1-PD00-PadP$33)") (class "Default")
      (node (ref "U$1") (pin "P$33") (pinfunction "PD00_P$33") (pintype "bidirectional"))
    )
    (net (code "83") (name "unconnected-(U$1-PD01-PadP$32)") (class "Default")
      (node (ref "U$1") (pin "P$32") (pinfunction "PD01_P$32") (pintype "bidirectional"))
    )
    (net (code "84") (name "unconnected-(U$1-PD02-PadP$31)") (class "Default")
      (node (ref "U$1") (pin "P$31") (pinfunction "PD02_P$31") (pintype "bidirectional"))
    )
    (net (code "85") (name "unconnected-(U$1-PD03-PadP$30)") (class "Default")
      (node (ref "U$1") (pin "P$30") (pinfunction "PD03_P$30") (pintype "bidirectional"))
    )
    (net (code "86") (name "unconnected-(U$1-VDCDC-PadP$24)") (class "Default")
      (node (ref "U$1") (pin "P$24") (pinfunction "VDCDC_P$24") (pintype "bidirectional"))
    )
    (net (code "87") (name "unconnected-(U9A-CHR0-Pad15)") (class "Default")
      (node (ref "U9") (pin "15") (pinfunction "CHR0_15") (pintype "output"))
    )
    (net (code "88") (name "unconnected-(U9A-CHR1-Pad14)") (class "Default")
      (node (ref "U9") (pin "14") (pinfunction "CHR1_14") (pintype "output"))
    )
    (net (code "89") (name "unconnected-(U9A-CHREN-Pad13)") (class "Default")
      (node (ref "U9") (pin "13") (pinfunction "CHREN_13") (pintype "output"))
    )
    (net (code "90") (name "unconnected-(U9A-CTS-Pad23)") (class "Default")
      (node (ref "U9") (pin "23") (pinfunction "CTS_23") (pintype "input"))
    )
    (net (code "91") (name "unconnected-(U9A-DCD-Pad1)") (class "Default")
      (node (ref "U9") (pin "1") (pinfunction "DCD_1") (pintype "input"))
    )
    (net (code "92") (name "unconnected-(U9A-DSR-Pad27)") (class "Default")
      (node (ref "U9") (pin "27") (pinfunction "DSR_27") (pintype "input"))
    )
    (net (code "93") (name "unconnected-(U9A-GPIO.0{slash}TXT-Pad19)") (class "Default")
      (node (ref "U9") (pin "19") (pinfunction "GPIO.0/TXT_19") (pintype "bidirectional"))
    )
    (net (code "94") (name "unconnected-(U9A-GPIO.1{slash}RXT-Pad18)") (class "Default")
      (node (ref "U9") (pin "18") (pinfunction "GPIO.1/RXT_18") (pintype "bidirectional"))
    )
    (net (code "95") (name "unconnected-(U9A-GPIO.2{slash}RS485-Pad17)") (class "Default")
      (node (ref "U9") (pin "17") (pinfunction "GPIO.2/RS485_17") (pintype "bidirectional"))
    )
    (net (code "96") (name "unconnected-(U9A-GPIO.3{slash}WAKEUP-Pad16)") (class "Default")
      (node (ref "U9") (pin "16") (pinfunction "GPIO.3/WAKEUP_16") (pintype "bidirectional"))
    )
    (net (code "97") (name "unconnected-(U9A-GPIO.4-Pad22)") (class "Default")
      (node (ref "U9") (pin "22") (pinfunction "GPIO.4_22") (pintype "bidirectional"))
    )
    (net (code "98") (name "unconnected-(U9A-GPIO.5-Pad21)") (class "Default")
      (node (ref "U9") (pin "21") (pinfunction "GPIO.5_21") (pintype "bidirectional"))
    )
    (net (code "99") (name "unconnected-(U9A-GPIO.6-Pad20)") (class "Default")
      (node (ref "U9") (pin "20") (pinfunction "GPIO.6_20") (pintype "bidirectional"))
    )
    (net (code "100") (name "unconnected-(U9A-RI{slash}CLK-Pad2)") (class "Default")
      (node (ref "U9") (pin "2") (pinfunction "RI/CLK_2") (pintype "bidirectional"))
    )
    (net (code "101") (name "unconnected-(U9A-SUSPEND-Pad12)") (class "Default")
      (node (ref "U9") (pin "12") (pinfunction "SUSPEND_12") (pintype "output"))
    )
    (net (code "102") (name "unconnected-(U9A-SUSPENDB-Pad11)") (class "Default")
      (node (ref "U9") (pin "11") (pinfunction "SUSPENDB_11") (pintype "output"))
    )
    (net (code "103") (name "unconnected-(U9B-NC-Pad10)") (class "Default")
      (node (ref "U9") (pin "10") (pinfunction "NC_10") (pintype "no_connect"))
    )
    (net (code "104") (name "unconnected-(U12-D1--Pad2)") (class "Default")
      (node (ref "U12") (pin "2") (pinfunction "D1-_2") (pintype "bidirectional"))
    )
    (net (code "105") (name "unconnected-(U12-NC_4-Pad9)") (class "Default")
      (node (ref "U12") (pin "9") (pinfunction "NC_4_9") (pintype "passive"))
    )
    (net (code "106") (name "unconnected-(U25-DNC-Pad5)") (class "Default")
      (node (ref "U25") (pin "5") (pinfunction "DNC_5") (pintype "passive"))
    )
    (net (code "107") (name "unconnected-(U25-DNC_2-Pad4)") (class "Default")
      (node (ref "U25") (pin "4") (pinfunction "DNC_2_4") (pintype "passive"))
    )
    (net (code "108") (name "unconnected-(U25-PGOOD-Pad6)") (class "Default")
      (node (ref "U25") (pin "6") (pinfunction "PGOOD_6") (pintype "passive"))
    )
    (net (code "109") (name "unconnected-(U25-V5V-Pad13)") (class "Default")
      (node (ref "U25") (pin "13") (pinfunction "V5V_13") (pintype "passive"))
    )
    (net (code "110") (name "unconnected-(U28-I032-Pad8)") (class "Default")
      (node (ref "U28") (pin "8") (pinfunction "I032_8") (pintype "bidirectional"))
    )
    (net (code "111") (name "unconnected-(U28-I033-Pad9)") (class "Default")
      (node (ref "U28") (pin "9") (pinfunction "I033_9") (pintype "bidirectional"))
    )
    (net (code "112") (name "unconnected-(U28-I034-Pad6)") (class "Default")
      (node (ref "U28") (pin "6") (pinfunction "I034_6") (pintype "input"))
    )
    (net (code "113") (name "unconnected-(U28-I035-Pad7)") (class "Default")
      (node (ref "U28") (pin "7") (pinfunction "I035_7") (pintype "input"))
    )
    (net (code "114") (name "unconnected-(U28-SCL{slash}CLK-Pad20)") (class "Default")
      (node (ref "U28") (pin "20") (pinfunction "SCL/CLK_20") (pintype "bidirectional"))
    )
    (net (code "115") (name "unconnected-(U28-SCS{slash}CMD-Pad19)") (class "Default")
      (node (ref "U28") (pin "19") (pinfunction "SCS/CMD_19") (pintype "bidirectional"))
    )
    (net (code "116") (name "unconnected-(U28-SD1{slash}SD1-Pad22)") (class "Default")
      (node (ref "U28") (pin "22") (pinfunction "SD1/SD1_22") (pintype "bidirectional"))
    )
    (net (code "117") (name "unconnected-(U28-SDO{slash}SD0-Pad21)") (class "Default")
      (node (ref "U28") (pin "21") (pinfunction "SDO/SD0_21") (pintype "bidirectional"))
    )
    (net (code "118") (name "unconnected-(U28-SENSOR_VN-Pad5)") (class "Default")
      (node (ref "U28") (pin "5") (pinfunction "SENSOR_VN_5") (pintype "input"))
    )
    (net (code "119") (name "unconnected-(U28-SENSOR_VP-Pad4)") (class "Default")
      (node (ref "U28") (pin "4") (pinfunction "SENSOR_VP_4") (pintype "input"))
    )
    (net (code "120") (name "unconnected-(U28-SHD{slash}SD2-Pad17)") (class "Default")
      (node (ref "U28") (pin "17") (pinfunction "SHD/SD2_17") (pintype "bidirectional"))
    )
    (net (code "121") (name "unconnected-(U28-SWP{slash}SD3-Pad18)") (class "Default")
      (node (ref "U28") (pin "18") (pinfunction "SWP/SD3_18") (pintype "bidirectional"))
    )
  )
)
